# 0003.net
KiCad netlist of a schematic drawn in EasyEDA
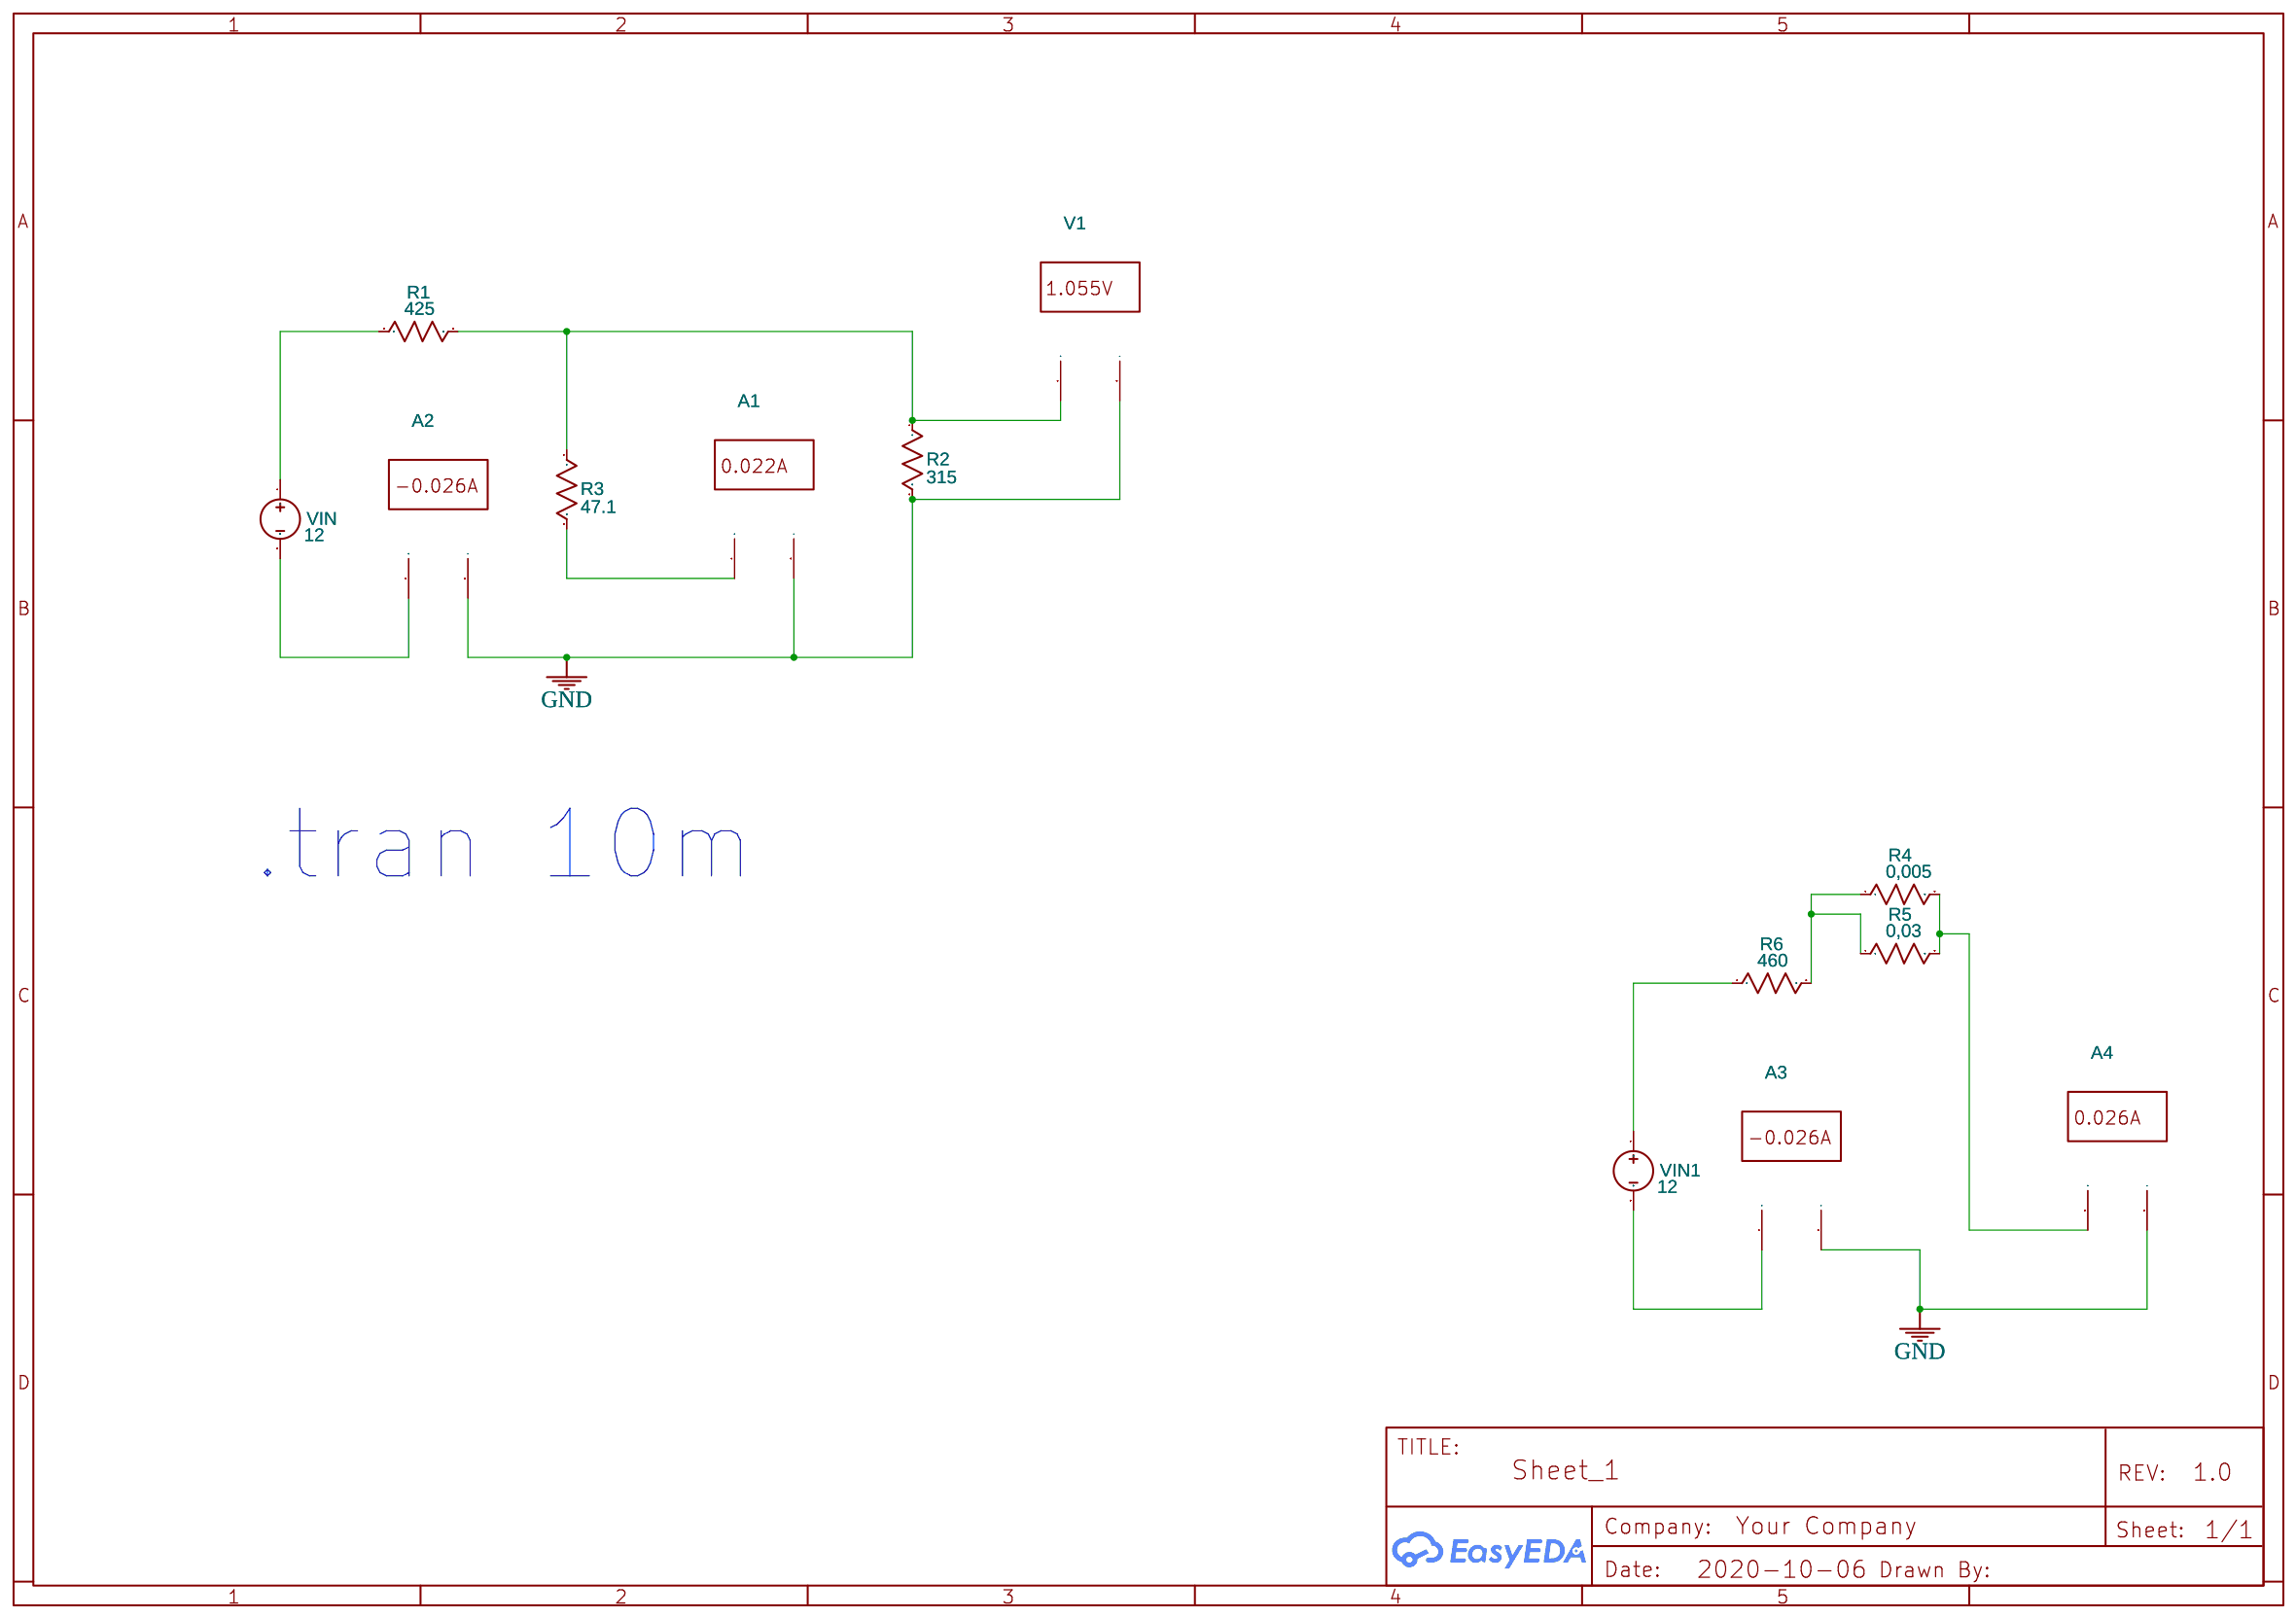
[diagram p0: schematic sheet]

(export (version "E")
  (design (tool "Eeschema 10.0.6"))
  (components
    (comp (ref "A1") (value "Multimeter") (libsource (lib "") (part "MULTIMETER_3")))
    (comp (ref "A2") (value "Multimeter") (libsource (lib "") (part "MULTIMETER")))
    (comp (ref "A3") (value "Multimeter") (libsource (lib "") (part "MULTIMETER")))
    (comp (ref "A4") (value "Multimeter") (libsource (lib "") (part "MULTIMETER_2")))
    (comp (ref "R1") (value "425") (libsource (lib "") (part "Resistor_US")))
    (comp (ref "R2") (value "315") (libsource (lib "") (part "Resistor_US_1")))
    (comp (ref "R3") (value "47.1") (libsource (lib "") (part "Resistor_US_1")))
    (comp (ref "R4") (value "0,005") (libsource (lib "") (part "Resistor_US")))
    (comp (ref "R5") (value "0,03") (libsource (lib "") (part "Resistor_US")))
    (comp (ref "R6") (value "460") (libsource (lib "") (part "Resistor_US")))
    (comp (ref "V1") (value "Multimeter") (libsource (lib "") (part "MULTIMETER_1")))
    (comp (ref "VIN") (value "12") (libsource (lib "") (part "VDC")))
    (comp (ref "VIN1") (value "12") (libsource (lib "") (part "VDC")))
  )
  (nets
    (net (code "1") (name "GND") (class "Default")
      (node (ref "A1") (pin "2") (pinfunction "I_2") (pintype "unspecified"))
      (node (ref "A2") (pin "2") (pinfunction "I_2") (pintype "unspecified"))
      (node (ref "A3") (pin "2") (pinfunction "I_2") (pintype "unspecified"))
      (node (ref "A4") (pin "2") (pinfunction "I_2") (pintype "unspecified"))
      (node (ref "R2") (pin "2") (pinfunction "2_2") (pintype "unspecified"))
      (node (ref "V1") (pin "2") (pinfunction "I_2") (pintype "unspecified"))
    )
    (net (code "2") (name "Net-(A1-+)") (class "Default")
      (node (ref "A1") (pin "1") (pinfunction "+_1") (pintype "unspecified"))
      (node (ref "R3") (pin "2") (pinfunction "2_2") (pintype "unspecified"))
    )
    (net (code "3") (name "Net-(A2-+)") (class "Default")
      (node (ref "A2") (pin "1") (pinfunction "+_1") (pintype "unspecified"))
      (node (ref "VIN") (pin "2") (pinfunction "2_2") (pintype "unspecified"))
    )
    (net (code "4") (name "Net-(A3-+)") (class "Default")
      (node (ref "A3") (pin "1") (pinfunction "+_1") (pintype "unspecified"))
      (node (ref "VIN1") (pin "2") (pinfunction "2_2") (pintype "unspecified"))
    )
    (net (code "5") (name "Net-(A4-+)") (class "Default")
      (node (ref "A4") (pin "1") (pinfunction "+_1") (pintype "unspecified"))
      (node (ref "R4") (pin "2") (pinfunction "2_2") (pintype "unspecified"))
      (node (ref "R5") (pin "2") (pinfunction "2_2") (pintype "unspecified"))
    )
    (net (code "6") (name "Net-(R1-Pad1)") (class "Default")
      (node (ref "R1") (pin "1") (pinfunction "1_1") (pintype "unspecified"))
      (node (ref "VIN") (pin "1") (pinfunction "1_1") (pintype "unspecified"))
    )
    (net (code "7") (name "Net-(R4-Pad1)") (class "Default")
      (node (ref "R4") (pin "1") (pinfunction "1_1") (pintype "unspecified"))
      (node (ref "R5") (pin "1") (pinfunction "1_1") (pintype "unspecified"))
      (node (ref "R6") (pin "2") (pinfunction "2_2") (pintype "unspecified"))
    )
    (net (code "8") (name "Net-(R6-Pad1)") (class "Default")
      (node (ref "R6") (pin "1") (pinfunction "1_1") (pintype "unspecified"))
      (node (ref "VIN1") (pin "1") (pinfunction "1_1") (pintype "unspecified"))
    )
    (net (code "9") (name "Net-(V1-+)") (class "Default")
      (node (ref "R1") (pin "2") (pinfunction "2_2") (pintype "unspecified"))
      (node (ref "R2") (pin "1") (pinfunction "1_1") (pintype "unspecified"))
      (node (ref "R3") (pin "1") (pinfunction "1_1") (pintype "unspecified"))
      (node (ref "V1") (pin "1") (pinfunction "+_1") (pintype "unspecified"))
    )
  )
)
